# fpga-bank4.net
KiCad netlist of a schematic drawn in Altium Designer
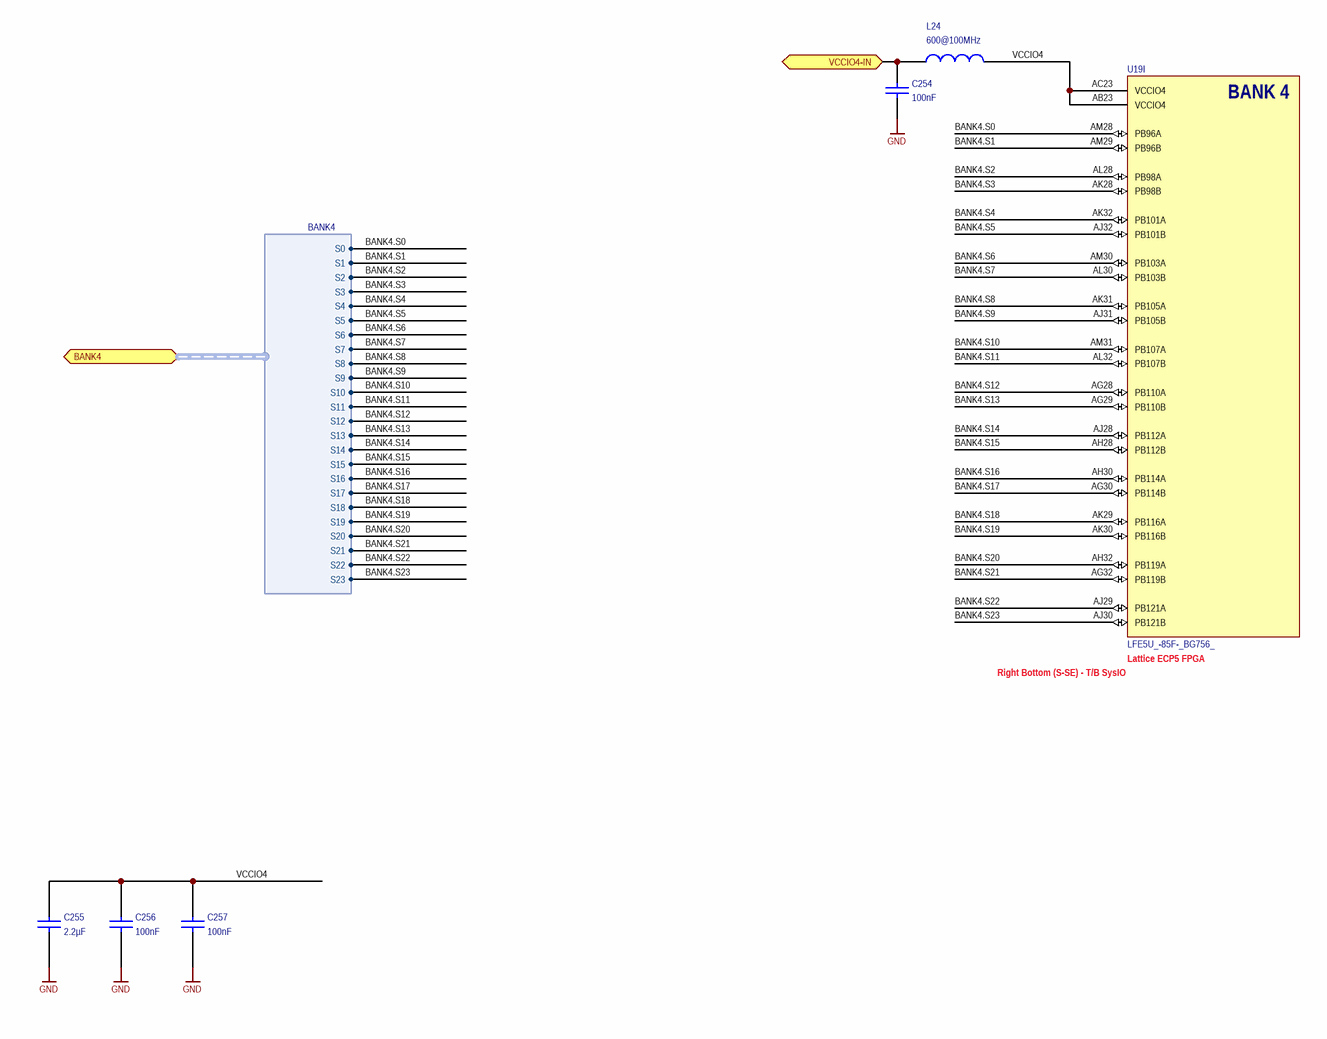
[diagram p0: fpga-bank4.SchDoc]

(export (version "E")
  (design (tool "Eeschema 10.0.6"))
  (components
    (comp (ref "C254")
      (value "100nF")
      (footprint "generic:CAPC1005X56N")
      (description "Ceramic Capacitor 100nF ±10% 16V X7R 0402")
      (fields (field (name "MANUFACTURER") "Murata") (field (name "TOLERANCE") "±10%"))
      (libsource (lib "murata") (part "GRM155R71A104KA01J"))
    )
    (comp (ref "C255")
      (value "2.2µF")
      (footprint "generic:CAPC1608X90N")
      (description "Ceramic Capacitor 2.2uF ±10% 10V X7R 0603")
      (fields (field (name "MANUFACTURER") "Murata") (field (name "TOLERANCE") "±10%"))
      (libsource (lib "murata") (part "GRM188R71A225KE15D"))
    )
    (comp (ref "C256")
      (value "100nF")
      (footprint "generic:CAPC1005X56N")
      (description "Ceramic Capacitor 100nF ±10% 16V X7R 0402")
      (fields (field (name "MANUFACTURER") "Murata") (field (name "TOLERANCE") "±10%"))
      (libsource (lib "murata") (part "GRM155R71A104KA01J"))
    )
    (comp (ref "C257")
      (value "100nF")
      (footprint "generic:CAPC1005X56N")
      (description "Ceramic Capacitor 100nF ±10% 16V X7R 0402")
      (fields (field (name "MANUFACTURER") "Murata") (field (name "TOLERANCE") "±10%"))
      (libsource (lib "murata") (part "GRM155R71A104KA01J"))
    )
    (comp (ref "L24")
      (value "600@100MHz")
      (footprint "0402")
      (description "Ferrite Bead 600-Ohm @ 100MHz 900mA 0402")
      (fields (field (name "MANUFACTURER") "Murata") (field (name "TOLERANCE") "±25%"))
      (libsource (lib "Graviton") (part "IND 0402"))
    )
    (comp (ref "U19")
      (value "LFE5U_-85F-_BG756_")
      (footprint "lattice:caBGA756")
      (description "ECP5 FPGA, 85k LUT, 756-caBGA")
      (fields (field (name "MANUFACTURER") "Lattice Semiconductor"))
      (libsource (lib "lattice") (part "LFE5U_-85F-_BG756_"))
    )
  )
  (nets
    (net (code "2") (name "/BANK4.S0") (class "Default")
      (node (ref "U19") (pin "AM28") (pinfunction "PB96A_AM28") (pintype "bidirectional"))
    )
    (net (code "3") (name "/BANK4.S1") (class "Default")
      (node (ref "U19") (pin "AM29") (pinfunction "PB96B_AM29") (pintype "bidirectional"))
    )
    (net (code "4") (name "/BANK4.S2") (class "Default")
      (node (ref "U19") (pin "AL28") (pinfunction "PB98A_AL28") (pintype "bidirectional"))
    )
    (net (code "5") (name "/BANK4.S3") (class "Default")
      (node (ref "U19") (pin "AK28") (pinfunction "PB98B_AK28") (pintype "bidirectional"))
    )
    (net (code "6") (name "/BANK4.S4") (class "Default")
      (node (ref "U19") (pin "AK32") (pinfunction "PB101A_AK32") (pintype "bidirectional"))
    )
    (net (code "7") (name "/BANK4.S5") (class "Default")
      (node (ref "U19") (pin "AJ32") (pinfunction "PB101B_AJ32") (pintype "bidirectional"))
    )
    (net (code "8") (name "/BANK4.S6") (class "Default")
      (node (ref "U19") (pin "AM30") (pinfunction "PB103A_AM30") (pintype "bidirectional"))
    )
    (net (code "9") (name "/BANK4.S7") (class "Default")
      (node (ref "U19") (pin "AL30") (pinfunction "PB103B_AL30") (pintype "bidirectional"))
    )
    (net (code "10") (name "/BANK4.S8") (class "Default")
      (node (ref "U19") (pin "AK31") (pinfunction "PB105A_AK31") (pintype "bidirectional"))
    )
    (net (code "11") (name "/BANK4.S9") (class "Default")
      (node (ref "U19") (pin "AJ31") (pinfunction "PB105B_AJ31") (pintype "bidirectional"))
    )
    (net (code "12") (name "/BANK4.S10") (class "Default")
      (node (ref "U19") (pin "AM31") (pinfunction "PB107A_AM31") (pintype "bidirectional"))
    )
    (net (code "13") (name "/BANK4.S11") (class "Default")
      (node (ref "U19") (pin "AL32") (pinfunction "PB107B_AL32") (pintype "bidirectional"))
    )
    (net (code "14") (name "/BANK4.S12") (class "Default")
      (node (ref "U19") (pin "AG28") (pinfunction "PB110A_AG28") (pintype "bidirectional"))
    )
    (net (code "15") (name "/BANK4.S13") (class "Default")
      (node (ref "U19") (pin "AG29") (pinfunction "PB110B_AG29") (pintype "bidirectional"))
    )
    (net (code "16") (name "/BANK4.S14") (class "Default")
      (node (ref "U19") (pin "AJ28") (pinfunction "PB112A_AJ28") (pintype "bidirectional"))
    )
    (net (code "17") (name "/BANK4.S15") (class "Default")
      (node (ref "U19") (pin "AH28") (pinfunction "PB112B_AH28") (pintype "bidirectional"))
    )
    (net (code "18") (name "/BANK4.S16") (class "Default")
      (node (ref "U19") (pin "AH30") (pinfunction "PB114A_AH30") (pintype "bidirectional"))
    )
    (net (code "19") (name "/BANK4.S17") (class "Default")
      (node (ref "U19") (pin "AG30") (pinfunction "PB114B_AG30") (pintype "bidirectional"))
    )
    (net (code "20") (name "/BANK4.S18") (class "Default")
      (node (ref "U19") (pin "AK29") (pinfunction "PB116A_AK29") (pintype "bidirectional"))
    )
    (net (code "21") (name "/BANK4.S19") (class "Default")
      (node (ref "U19") (pin "AK30") (pinfunction "PB116B_AK30") (pintype "bidirectional"))
    )
    (net (code "22") (name "/BANK4.S20") (class "Default")
      (node (ref "U19") (pin "AH32") (pinfunction "PB119A_AH32") (pintype "bidirectional"))
    )
    (net (code "23") (name "/BANK4.S21") (class "Default")
      (node (ref "U19") (pin "AG32") (pinfunction "PB119B_AG32") (pintype "bidirectional"))
    )
    (net (code "24") (name "/BANK4.S22") (class "Default")
      (node (ref "U19") (pin "AJ29") (pinfunction "PB121A_AJ29") (pintype "bidirectional"))
    )
    (net (code "25") (name "/BANK4.S23") (class "Default")
      (node (ref "U19") (pin "AJ30") (pinfunction "PB121B_AJ30") (pintype "bidirectional"))
    )
    (net (code "26") (name "/VCCIO4") (class "Default")
      (node (ref "C255") (pin "2") (pinfunction "2_2") (pintype "passive"))
      (node (ref "C256") (pin "2") (pinfunction "2_2") (pintype "passive"))
      (node (ref "C257") (pin "2") (pinfunction "2_2") (pintype "passive"))
      (node (ref "L24") (pin "1") (pinfunction "1_1") (pintype "passive"))
      (node (ref "U19") (pin "AB23") (pinfunction "VCCIO4_AB23") (pintype "power_in"))
      (node (ref "U19") (pin "AC23") (pinfunction "VCCIO4_AC23") (pintype "power_in"))
    )
    (net (code "27") (name "/VCCIO4-IN") (class "Default")
      (node (ref "C254") (pin "2") (pinfunction "2_2") (pintype "passive"))
      (node (ref "L24") (pin "2") (pinfunction "2_2") (pintype "passive"))
    )
    (net (code "29") (name "GND") (class "Default")
      (node (ref "C254") (pin "1") (pinfunction "1_1") (pintype "passive"))
      (node (ref "C255") (pin "1") (pinfunction "1_1") (pintype "passive"))
      (node (ref "C256") (pin "1") (pinfunction "1_1") (pintype "passive"))
      (node (ref "C257") (pin "1") (pinfunction "1_1") (pintype "passive"))
    )
  )
)
